# leo_sch.net
KiCad netlist of a schematic drawn in Altium Designer
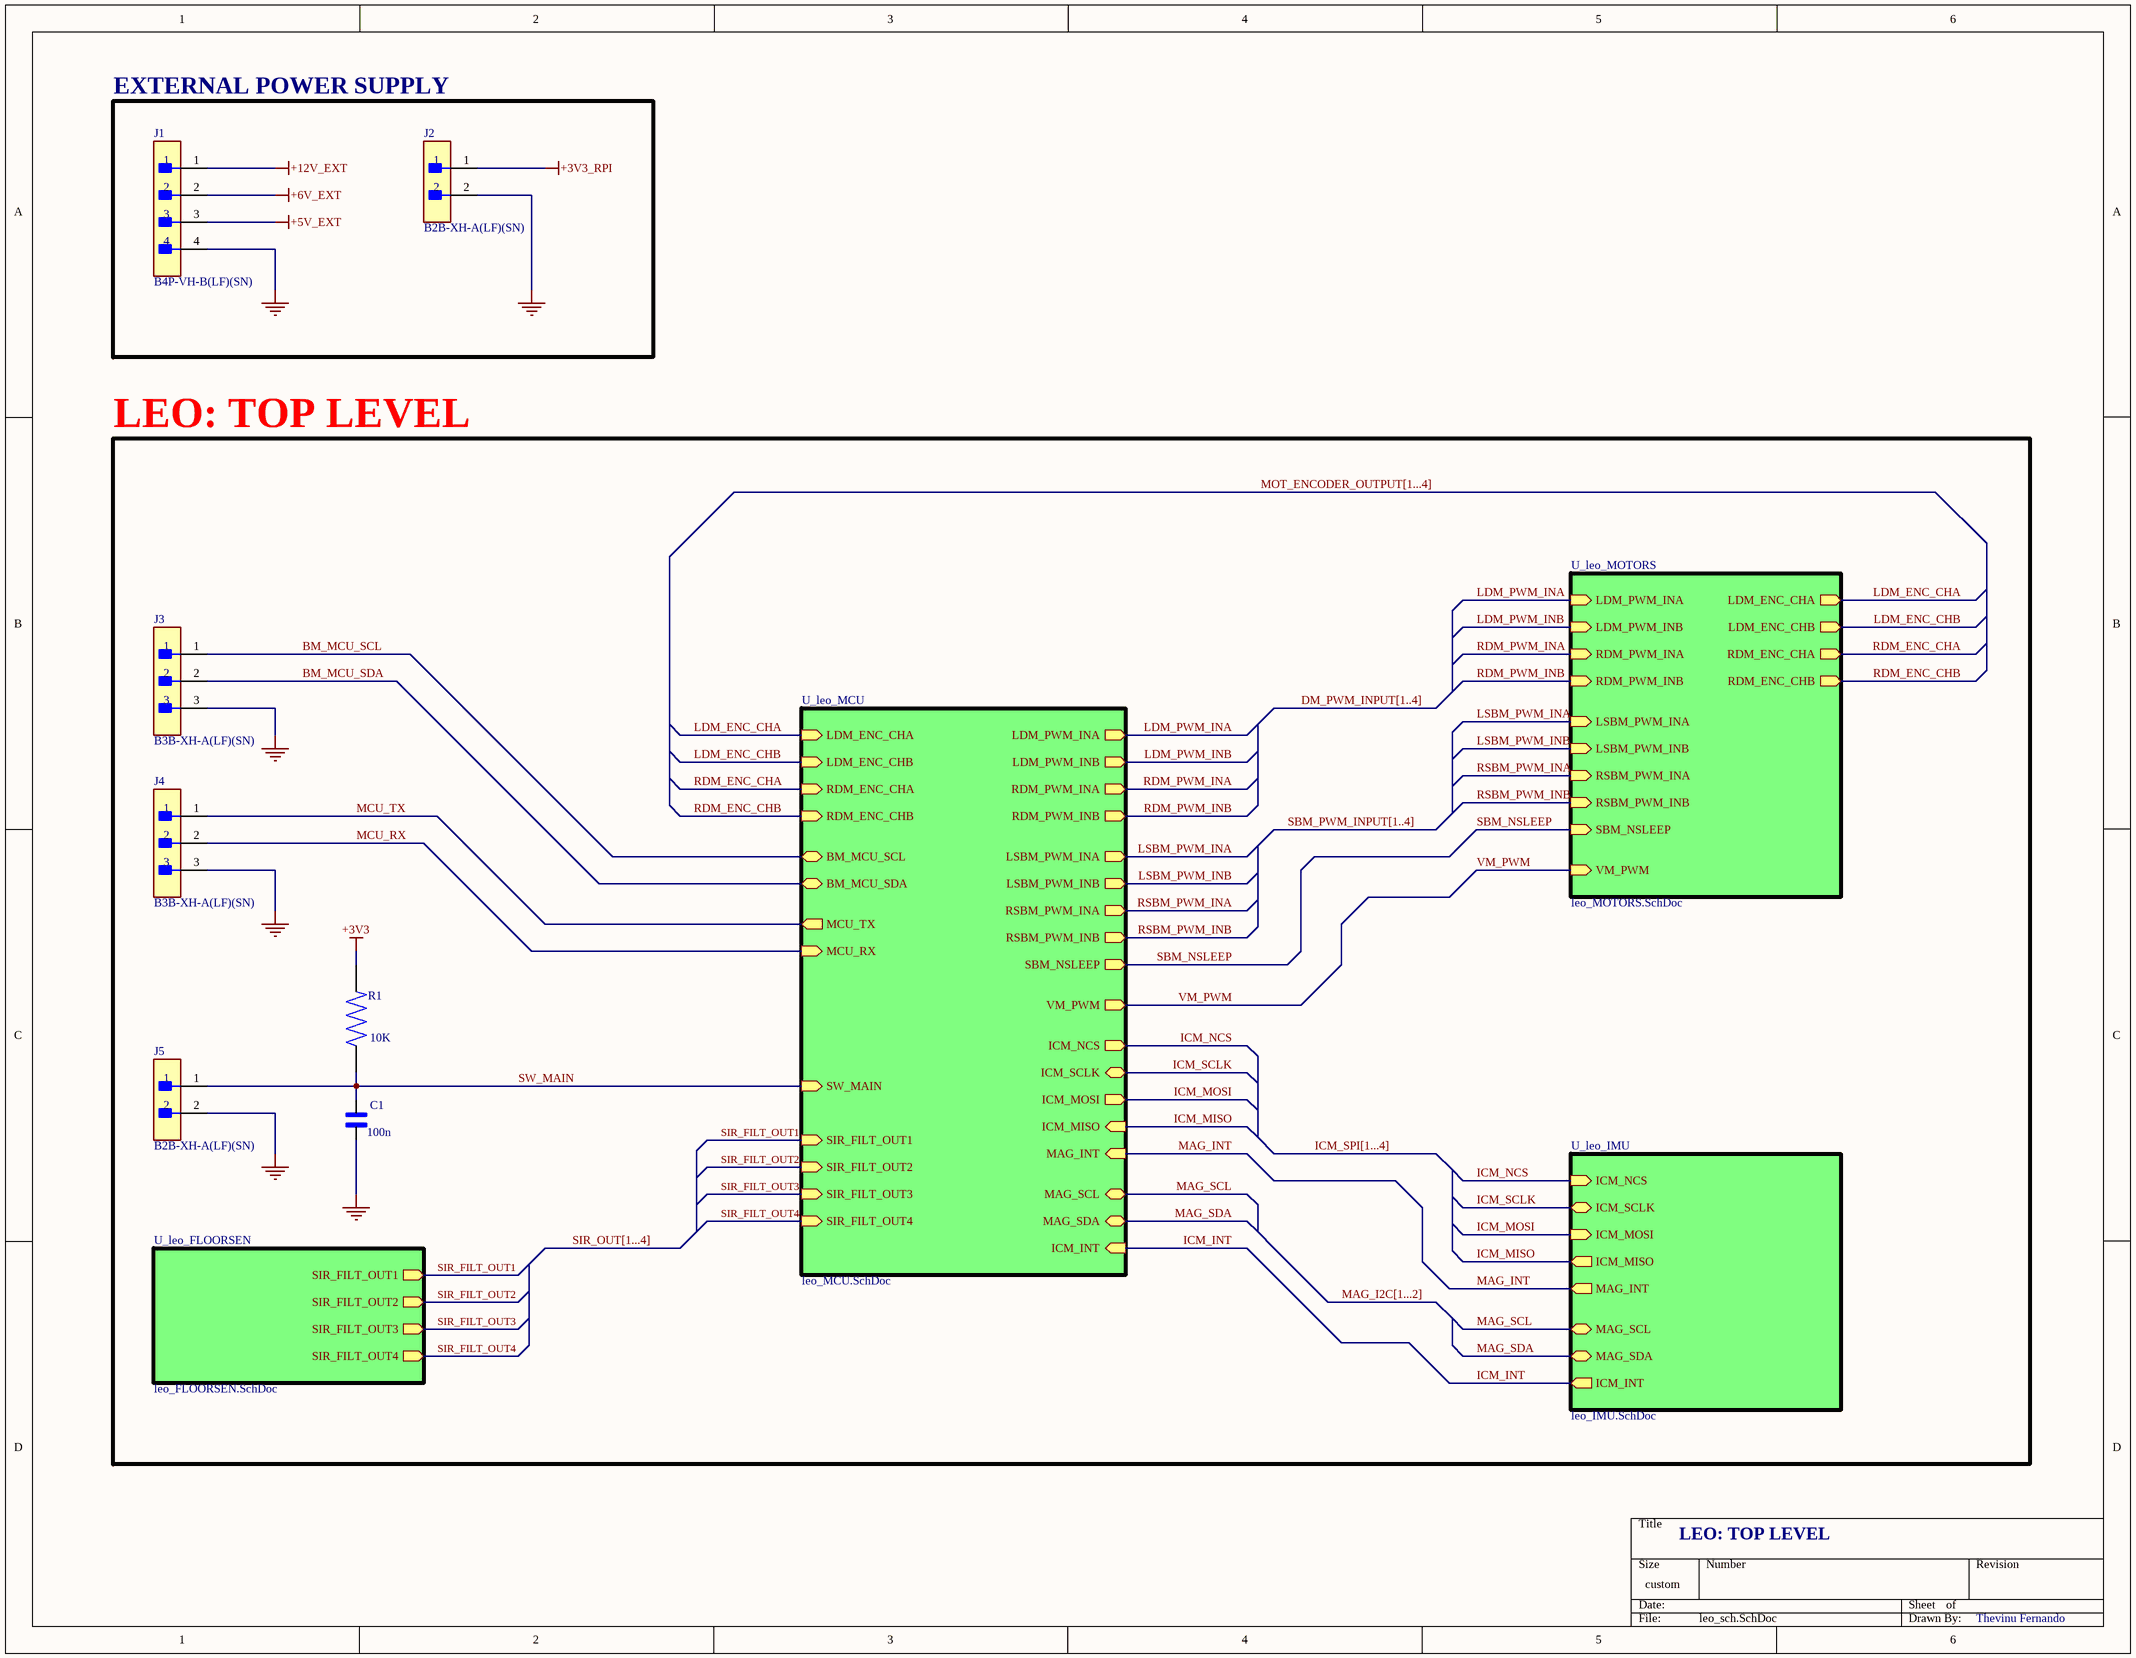
[diagram p0: leo_sch.SchDoc]

(export (version "E")
  (design (tool "Eeschema 10.0.6"))
  (components
    (comp (ref "C1")
      (value "100n")
      (footprint "CAP_0402")
      (description "Ceramic Capacitor X7R 0402 (1005 Metric)")
      (fields (field (name "MF") "Samsung") (field (name "MP") "CL05B104KO5NNNC"))
      (libsource (lib "leo_schlib") (part "CAP_0402"))
    )
    (comp (ref "J1")
      (value "B4P-VH-B(LF)(SN)")
      (footprint "FP-B4P-VH-B_LF_SN-MFG")
      (description "CONN HEADER VERT 4POS 3.96MM")
      (libsource (lib "leo_schlib") (part "B4P-VH-B(LF)(SN)"))
    )
    (comp (ref "J2")
      (value "B2B-XH-A(LF)(SN)")
      (footprint "FP-B2B-XH-A_LF_SN-MFG")
      (description "CONN HEADER VERT 2POS 2.5MM")
      (libsource (lib "leo_schlib") (part "B2B-XH-A(LF)(SN)"))
    )
    (comp (ref "J3")
      (value "B3B-XH-A(LF)(SN)")
      (footprint "FP-B3B-XH-A_LF_SN-MFG")
      (description "CONN HEADER VERT 3POS 2.5MM")
      (libsource (lib "leo_schlib") (part "B3B-XH-A(LF)(SN)"))
    )
    (comp (ref "J4")
      (value "B3B-XH-A(LF)(SN)")
      (footprint "FP-B3B-XH-A_LF_SN-MFG")
      (description "CONN HEADER VERT 3POS 2.5MM")
      (libsource (lib "leo_schlib") (part "B3B-XH-A(LF)(SN)"))
    )
    (comp (ref "J5")
      (value "B2B-XH-A(LF)(SN)")
      (footprint "FP-B2B-XH-A_LF_SN-MFG")
      (description "CONN HEADER VERT 2POS 2.5MM")
      (libsource (lib "leo_schlib") (part "B2B-XH-A(LF)(SN)"))
    )
    (comp (ref "R1")
      (value "10K")
      (footprint "RES_0402")
      (description "Chip Resistor 0402 (1005 Metric) Automotive AEC-Q200 Thick Film")
      (fields (field (name "MF") "Panasonic") (field (name "MP") "ERJ-2RKF1002X"))
      (libsource (lib "leo_schlib") (part "RES_0402"))
    )
  )
  (nets
    (net (code "13") (name "+3V3") (class "Default")
      (node (ref "R1") (pin "2") (pinfunction "2_2") (pintype "passive"))
    )
    (net (code "14") (name "+3V3_RPI") (class "Default")
      (node (ref "J2") (pin "1") (pinfunction "1_1") (pintype "passive"))
    )
    (net (code "15") (name "+5V_EXT") (class "Default")
      (node (ref "J1") (pin "3") (pinfunction "3_3") (pintype "passive"))
    )
    (net (code "16") (name "+6V_EXT") (class "Default")
      (node (ref "J1") (pin "2") (pinfunction "2_2") (pintype "passive"))
    )
    (net (code "17") (name "+12V_EXT") (class "Default")
      (node (ref "J1") (pin "1") (pinfunction "1_1") (pintype "passive"))
    )
    (net (code "18") (name "/BM_MCU_SCL") (class "Default")
      (node (ref "J3") (pin "1") (pinfunction "1_1") (pintype "passive"))
    )
    (net (code "19") (name "/BM_MCU_SDA") (class "Default")
      (node (ref "J3") (pin "2") (pinfunction "2_2") (pintype "passive"))
    )
    (net (code "35") (name "/MCU_RX") (class "Default")
      (node (ref "J4") (pin "2") (pinfunction "2_2") (pintype "passive"))
    )
    (net (code "36") (name "/MCU_TX") (class "Default")
      (node (ref "J4") (pin "1") (pinfunction "1_1") (pintype "passive"))
    )
    (net (code "49") (name "/SW_MAIN") (class "Default")
      (node (ref "C1") (pin "2") (pinfunction "2_2") (pintype "passive"))
      (node (ref "J5") (pin "1") (pinfunction "1_1") (pintype "passive"))
      (node (ref "R1") (pin "1") (pinfunction "1_1") (pintype "passive"))
    )
    (net (code "55") (name "GND") (class "Default")
      (node (ref "C1") (pin "1") (pinfunction "1_1") (pintype "passive"))
      (node (ref "J1") (pin "4") (pinfunction "4_4") (pintype "passive"))
      (node (ref "J2") (pin "2") (pinfunction "2_2") (pintype "passive"))
      (node (ref "J3") (pin "3") (pinfunction "3_3") (pintype "passive"))
      (node (ref "J4") (pin "3") (pinfunction "3_3") (pintype "passive"))
      (node (ref "J5") (pin "2") (pinfunction "2_2") (pintype "passive"))
    )
  )
)
